# Schematic.net
KiCad netlist of a schematic drawn in EAGLE
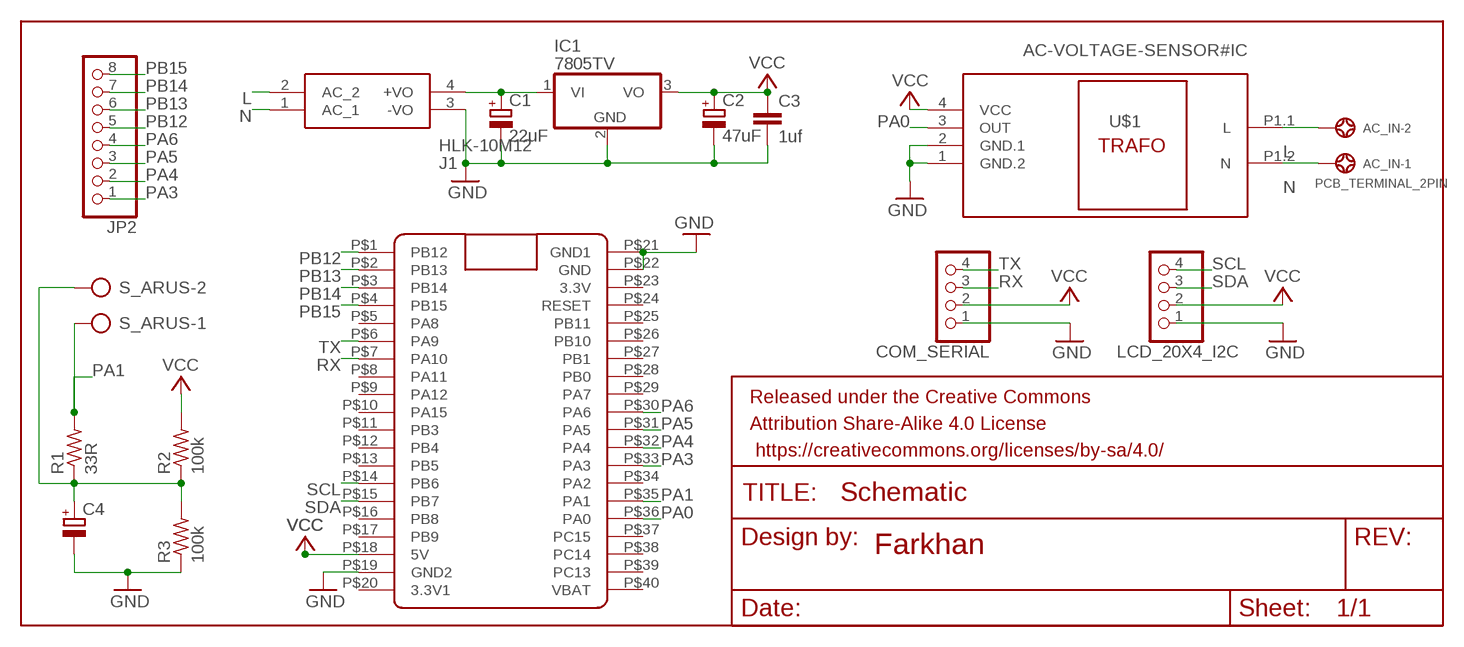
[diagram p0: schematic, sheet 1]

(export (version "E")
  (design (tool "Eeschema 10.0.6"))
  (components
    (comp (ref "AC_IN")
      (value "PCB_TERMINAL_2PIN")
      (footprint "eagle-import:PCB_TERMINAL_2PIN")
      (libsource (lib "eagle-import") (part "PCB_TERMINAL_2PIN"))
    )
    (comp (ref "C1")
      (value "22uF")
      (footprint "eagle-import:E2,5-7")
      (libsource (lib "eagle-import") (part "CPOL-EUE2.5-7"))
    )
    (comp (ref "C2")
      (value "47uF")
      (footprint "eagle-import:E2,5-7")
      (libsource (lib "eagle-import") (part "CPOL-EUE2.5-7"))
    )
    (comp (ref "C3")
      (value "1uf")
      (footprint "eagle-import:C050-025X075")
      (libsource (lib "eagle-import") (part "C-EU050-025X075"))
    )
    (comp (ref "C4")
      (value "CPOL-EUE2.5-6")
      (footprint "eagle-import:E2,5-6")
      (libsource (lib "eagle-import") (part "CPOL-EUE2.5-6"))
    )
    (comp (ref "COM_SERIAL")
      (value "PINHD-1X4")
      (footprint "eagle-import:1X04")
      (libsource (lib "eagle-import") (part "PINHD-1X4"))
    )
    (comp (ref "FRAME1")
      (value "FRAME-LEDGER")
      (footprint "eagle-import:CREATIVE_COMMONS")
      (libsource (lib "eagle-import") (part "FRAME-LEDGER"))
    )
    (comp (ref "IC1")
      (value "7805TV")
      (footprint "eagle-import:TO220V")
      (libsource (lib "eagle-import") (part "78TV05"))
    )
    (comp (ref "J1")
      (value "HLK-10M12")
      (footprint "eagle-import:HLK10M12")
      (libsource (lib "eagle-import") (part "HLK-10M12"))
    )
    (comp (ref "JP2")
      (value "PINHD-1X8")
      (footprint "eagle-import:1X08")
      (libsource (lib "eagle-import") (part "PINHD-1X8"))
    )
    (comp (ref "LCD_20X4_I2C")
      (value "PINHD-1X4")
      (footprint "eagle-import:1X04")
      (libsource (lib "eagle-import") (part "PINHD-1X4"))
    )
    (comp (ref "R1")
      (value "33R")
      (footprint "eagle-import:0207_10")
      (libsource (lib "eagle-import") (part "R-US_0207/10"))
    )
    (comp (ref "R2")
      (value "100k")
      (footprint "eagle-import:0207_10")
      (libsource (lib "eagle-import") (part "R-US_0207/10"))
    )
    (comp (ref "R3")
      (value "100k")
      (footprint "eagle-import:0207_10")
      (libsource (lib "eagle-import") (part "R-US_0207/10"))
    )
    (comp (ref "S_ARUS")
      (value "AK500/2")
      (footprint "eagle-import:AK500_2")
      (libsource (lib "eagle-import") (part "AK500/2"))
    )
    (comp (ref "U$1")
      (value "AC-VOLTAGE-SENSOR#IC")
      (footprint "eagle-import:AC-VOLTAGE-SENSOR#IC")
      (libsource (lib "eagle-import") (part "AC-VOLTAGE-SENSOR#IC"))
    )
    (comp (ref "U$2")
      (value "BLUE_PILL")
      (footprint "eagle-import:BLUE_PILL")
      (libsource (lib "eagle-import") (part "BLUE_PILL"))
    )
  )
  (nets
    (net (code "1") (name "/L") (class "Default")
      (node (ref "AC_IN") (pin "2") (pinfunction "1_2") (pintype "passive"))
      (node (ref "J1") (pin "2") (pinfunction "AC_2_2") (pintype "bidirectional"))
      (node (ref "U$1") (pin "P1.1") (pinfunction "L_P1.1") (pintype "passive"))
    )
    (net (code "2") (name "/N") (class "Default")
      (node (ref "AC_IN") (pin "1") (pinfunction "1_1") (pintype "passive"))
      (node (ref "J1") (pin "1") (pinfunction "AC_1_1") (pintype "bidirectional"))
      (node (ref "U$1") (pin "P1.2") (pinfunction "N_P1.2") (pintype "passive"))
    )
    (net (code "3") (name "/PA0") (class "Default")
      (node (ref "U$1") (pin "3") (pinfunction "OUT_3") (pintype "output"))
      (node (ref "U$2") (pin "P$36") (pinfunction "PA0_P$36") (pintype "bidirectional"))
    )
    (net (code "4") (name "/PA1") (class "Default")
      (node (ref "R1") (pin "2") (pinfunction "2_2") (pintype "passive"))
      (node (ref "S_ARUS") (pin "1") (pinfunction "KL_1") (pintype "passive"))
      (node (ref "U$2") (pin "P$35") (pinfunction "PA1_P$35") (pintype "bidirectional"))
    )
    (net (code "5") (name "/PA3") (class "Default")
      (node (ref "JP2") (pin "1") (pinfunction "1_1") (pintype "passive"))
      (node (ref "U$2") (pin "P$33") (pinfunction "PA3_P$33") (pintype "bidirectional"))
    )
    (net (code "6") (name "/PA4") (class "Default")
      (node (ref "JP2") (pin "2") (pinfunction "2_2") (pintype "passive"))
      (node (ref "U$2") (pin "P$32") (pinfunction "PA4_P$32") (pintype "bidirectional"))
    )
    (net (code "7") (name "/PA5") (class "Default")
      (node (ref "JP2") (pin "3") (pinfunction "3_3") (pintype "passive"))
      (node (ref "U$2") (pin "P$31") (pinfunction "PA5_P$31") (pintype "bidirectional"))
    )
    (net (code "8") (name "/PA6") (class "Default")
      (node (ref "JP2") (pin "4") (pinfunction "4_4") (pintype "passive"))
      (node (ref "U$2") (pin "P$30") (pinfunction "PA6_P$30") (pintype "bidirectional"))
    )
    (net (code "9") (name "/PB12") (class "Default")
      (node (ref "JP2") (pin "5") (pinfunction "5_5") (pintype "passive"))
      (node (ref "U$2") (pin "P$1") (pinfunction "PB12_P$1") (pintype "bidirectional"))
    )
    (net (code "10") (name "/PB13") (class "Default")
      (node (ref "JP2") (pin "6") (pinfunction "6_6") (pintype "passive"))
      (node (ref "U$2") (pin "P$2") (pinfunction "PB13_P$2") (pintype "bidirectional"))
    )
    (net (code "11") (name "/PB14") (class "Default")
      (node (ref "JP2") (pin "7") (pinfunction "7_7") (pintype "passive"))
      (node (ref "U$2") (pin "P$3") (pinfunction "PB14_P$3") (pintype "bidirectional"))
    )
    (net (code "12") (name "/PB15") (class "Default")
      (node (ref "JP2") (pin "8") (pinfunction "8_8") (pintype "passive"))
      (node (ref "U$2") (pin "P$4") (pinfunction "PB15_P$4") (pintype "bidirectional"))
    )
    (net (code "13") (name "/RX") (class "Default")
      (node (ref "COM_SERIAL") (pin "3") (pinfunction "3_3") (pintype "passive"))
      (node (ref "U$2") (pin "P$7") (pinfunction "PA10_P$7") (pintype "bidirectional"))
    )
    (net (code "14") (name "/SCL") (class "Default")
      (node (ref "LCD_20X4_I2C") (pin "4") (pinfunction "4_4") (pintype "passive"))
      (node (ref "U$2") (pin "P$14") (pinfunction "PB6_P$14") (pintype "bidirectional"))
    )
    (net (code "15") (name "/SDA") (class "Default")
      (node (ref "LCD_20X4_I2C") (pin "3") (pinfunction "3_3") (pintype "passive"))
      (node (ref "U$2") (pin "P$15") (pinfunction "PB7_P$15") (pintype "bidirectional"))
    )
    (net (code "16") (name "/TX") (class "Default")
      (node (ref "COM_SERIAL") (pin "4") (pinfunction "4_4") (pintype "passive"))
      (node (ref "U$2") (pin "P$6") (pinfunction "PA9_P$6") (pintype "bidirectional"))
    )
    (net (code "17") (name "GND") (class "Default")
      (node (ref "C1") (pin "-") (pinfunction "-_-") (pintype "passive"))
      (node (ref "C2") (pin "-") (pinfunction "-_-") (pintype "passive"))
      (node (ref "C3") (pin "2") (pinfunction "2_2") (pintype "passive"))
      (node (ref "C4") (pin "-") (pinfunction "-_-") (pintype "passive"))
      (node (ref "COM_SERIAL") (pin "1") (pinfunction "1_1") (pintype "passive"))
      (node (ref "IC1") (pin "2") (pinfunction "GND_2") (pintype "passive"))
      (node (ref "J1") (pin "3") (pinfunction "-VO_3") (pintype "bidirectional"))
      (node (ref "LCD_20X4_I2C") (pin "1") (pinfunction "1_1") (pintype "passive"))
      (node (ref "R3") (pin "1") (pinfunction "1_1") (pintype "passive"))
      (node (ref "U$1") (pin "1") (pinfunction "GND.2_1") (pintype "power_in"))
      (node (ref "U$1") (pin "2") (pinfunction "GND.1_2") (pintype "power_in"))
      (node (ref "U$2") (pin "P$19") (pinfunction "GND2_P$19") (pintype "bidirectional"))
      (node (ref "U$2") (pin "P$21") (pinfunction "GND1_P$21") (pintype "power_in"))
      (node (ref "U$2") (pin "P$22") (pinfunction "GND_P$22") (pintype "bidirectional"))
    )
    (net (code "18") (name "Net-(IC1-VI)") (class "Default")
      (node (ref "C1") (pin "+") (pinfunction "+_+") (pintype "passive"))
      (node (ref "IC1") (pin "1") (pinfunction "VI_1") (pintype "input"))
      (node (ref "J1") (pin "4") (pinfunction "+VO_4") (pintype "bidirectional"))
    )
    (net (code "19") (name "Net-(S_ARUSB-KL)") (class "Default")
      (node (ref "C4") (pin "+") (pinfunction "+_+") (pintype "passive"))
      (node (ref "R1") (pin "1") (pinfunction "1_1") (pintype "passive"))
      (node (ref "R2") (pin "1") (pinfunction "1_1") (pintype "passive"))
      (node (ref "R3") (pin "2") (pinfunction "2_2") (pintype "passive"))
      (node (ref "S_ARUS") (pin "2") (pinfunction "KL_2") (pintype "passive"))
    )
    (net (code "20") (name "VCC") (class "Default")
      (node (ref "C2") (pin "+") (pinfunction "+_+") (pintype "passive"))
      (node (ref "C3") (pin "1") (pinfunction "1_1") (pintype "passive"))
      (node (ref "COM_SERIAL") (pin "2") (pinfunction "2_2") (pintype "passive"))
      (node (ref "IC1") (pin "3") (pinfunction "VO_3") (pintype "passive"))
      (node (ref "LCD_20X4_I2C") (pin "2") (pinfunction "2_2") (pintype "passive"))
      (node (ref "R2") (pin "2") (pinfunction "2_2") (pintype "passive"))
      (node (ref "U$1") (pin "4") (pinfunction "VCC_4") (pintype "power_in"))
      (node (ref "U$2") (pin "P$18") (pinfunction "5V_P$18") (pintype "bidirectional"))
    )
    (net (code "21") (name "unconnected-(U$2-3.3V-PadP$23)") (class "Default")
      (node (ref "U$2") (pin "P$23") (pinfunction "3.3V_P$23") (pintype "bidirectional"))
    )
    (net (code "22") (name "unconnected-(U$2-3.3V1-PadP$20)") (class "Default")
      (node (ref "U$2") (pin "P$20") (pinfunction "3.3V1_P$20") (pintype "bidirectional"))
    )
    (net (code "23") (name "unconnected-(U$2-PA2-PadP$34)") (class "Default")
      (node (ref "U$2") (pin "P$34") (pinfunction "PA2_P$34") (pintype "bidirectional"))
    )
    (net (code "24") (name "unconnected-(U$2-PA7-PadP$29)") (class "Default")
      (node (ref "U$2") (pin "P$29") (pinfunction "PA7_P$29") (pintype "bidirectional"))
    )
    (net (code "25") (name "unconnected-(U$2-PA8-PadP$5)") (class "Default")
      (node (ref "U$2") (pin "P$5") (pinfunction "PA8_P$5") (pintype "bidirectional"))
    )
    (net (code "26") (name "unconnected-(U$2-PA11-PadP$8)") (class "Default")
      (node (ref "U$2") (pin "P$8") (pinfunction "PA11_P$8") (pintype "bidirectional"))
    )
    (net (code "27") (name "unconnected-(U$2-PA12-PadP$9)") (class "Default")
      (node (ref "U$2") (pin "P$9") (pinfunction "PA12_P$9") (pintype "bidirectional"))
    )
    (net (code "28") (name "unconnected-(U$2-PA15-PadP$10)") (class "Default")
      (node (ref "U$2") (pin "P$10") (pinfunction "PA15_P$10") (pintype "bidirectional"))
    )
    (net (code "29") (name "unconnected-(U$2-PB0-PadP$28)") (class "Default")
      (node (ref "U$2") (pin "P$28") (pinfunction "PB0_P$28") (pintype "bidirectional"))
    )
    (net (code "30") (name "unconnected-(U$2-PB1-PadP$27)") (class "Default")
      (node (ref "U$2") (pin "P$27") (pinfunction "PB1_P$27") (pintype "bidirectional"))
    )
    (net (code "31") (name "unconnected-(U$2-PB3-PadP$11)") (class "Default")
      (node (ref "U$2") (pin "P$11") (pinfunction "PB3_P$11") (pintype "bidirectional"))
    )
    (net (code "32") (name "unconnected-(U$2-PB4-PadP$12)") (class "Default")
      (node (ref "U$2") (pin "P$12") (pinfunction "PB4_P$12") (pintype "bidirectional"))
    )
    (net (code "33") (name "unconnected-(U$2-PB5-PadP$13)") (class "Default")
      (node (ref "U$2") (pin "P$13") (pinfunction "PB5_P$13") (pintype "bidirectional"))
    )
    (net (code "34") (name "unconnected-(U$2-PB8-PadP$16)") (class "Default")
      (node (ref "U$2") (pin "P$16") (pinfunction "PB8_P$16") (pintype "bidirectional"))
    )
    (net (code "35") (name "unconnected-(U$2-PB9-PadP$17)") (class "Default")
      (node (ref "U$2") (pin "P$17") (pinfunction "PB9_P$17") (pintype "bidirectional"))
    )
    (net (code "36") (name "unconnected-(U$2-PB10-PadP$26)") (class "Default")
      (node (ref "U$2") (pin "P$26") (pinfunction "PB10_P$26") (pintype "bidirectional"))
    )
    (net (code "37") (name "unconnected-(U$2-PB11-PadP$25)") (class "Default")
      (node (ref "U$2") (pin "P$25") (pinfunction "PB11_P$25") (pintype "bidirectional"))
    )
    (net (code "38") (name "unconnected-(U$2-PC13-PadP$39)") (class "Default")
      (node (ref "U$2") (pin "P$39") (pinfunction "PC13_P$39") (pintype "bidirectional"))
    )
    (net (code "39") (name "unconnected-(U$2-PC14-PadP$38)") (class "Default")
      (node (ref "U$2") (pin "P$38") (pinfunction "PC14_P$38") (pintype "bidirectional"))
    )
    (net (code "40") (name "unconnected-(U$2-PC15-PadP$37)") (class "Default")
      (node (ref "U$2") (pin "P$37") (pinfunction "PC15_P$37") (pintype "bidirectional"))
    )
    (net (code "41") (name "unconnected-(U$2-RESET-PadP$24)") (class "Default")
      (node (ref "U$2") (pin "P$24") (pinfunction "RESET_P$24") (pintype "bidirectional"))
    )
    (net (code "42") (name "unconnected-(U$2-VBAT-PadP$40)") (class "Default")
      (node (ref "U$2") (pin "P$40") (pinfunction "VBAT_P$40") (pintype "bidirectional"))
    )
  )
)
